# IMU_Breakout_Board.net
KiCad netlist of a schematic drawn in EAGLE
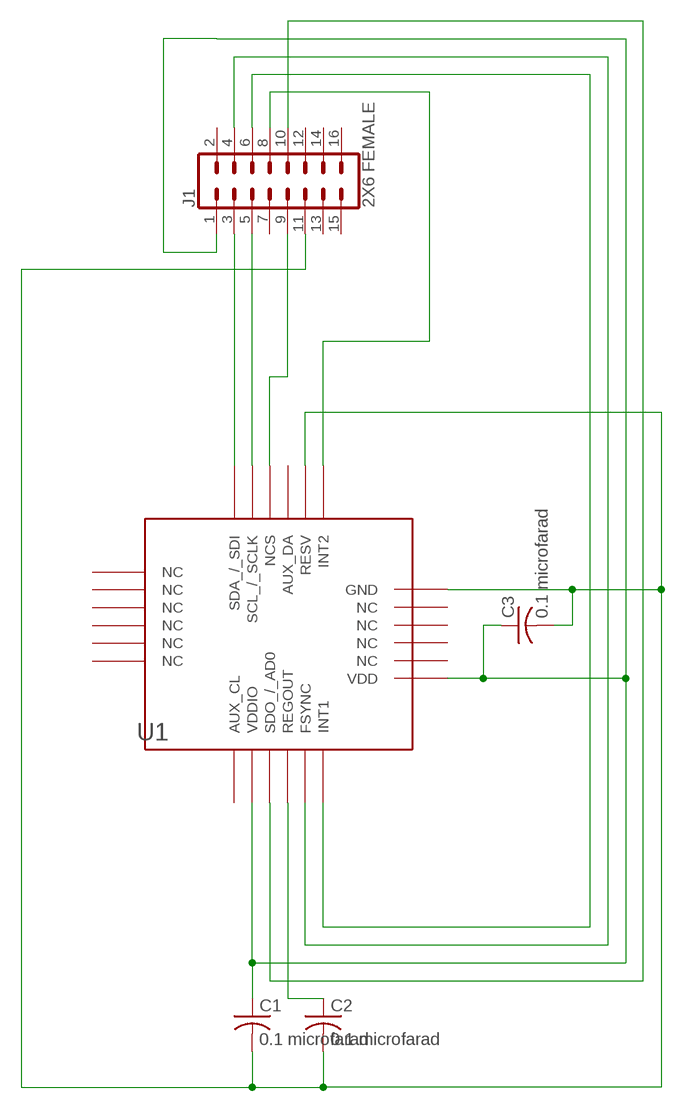
[diagram p0: schematic, sheet 1]

(export (version "E")
  (design (tool "Eeschema 10.0.6"))
  (components
    (comp (ref "C1")
      (value "0.1 microfarad")
      (footprint "eagle-import:C1206")
      (libsource (lib "eagle-import") (part "C-ALL_PACKAGESC1206"))
    )
    (comp (ref "C2")
      (value "0.1 microfarad")
      (footprint "eagle-import:C1206")
      (libsource (lib "eagle-import") (part "C-ALL_PACKAGESC1206"))
    )
    (comp (ref "C3")
      (value "0.1 microfarad")
      (footprint "eagle-import:C1206")
      (libsource (lib "eagle-import") (part "C-ALL_PACKAGESC1206"))
    )
    (comp (ref "J1")
      (value "2X6 FEMALE")
      (footprint "eagle-import:2X7")
      (libsource (lib "eagle-import") (part "SENSOR_BREAKOUTPTH_FEMALE"))
    )
    (comp (ref "U1")
      (value "ICM_20649")
      (footprint "eagle-import:ICM-20649")
      (libsource (lib "eagle-import") (part "ICM_20649"))
    )
  )
  (nets
    (net (code "1") (name "Net-(U1-FSYNC)") (class "Default")
      (node (ref "J1") (pin "4") (pinfunction "4_4") (pintype "passive"))
      (node (ref "U1") (pin "P4") (pinfunction "FSYNC_P4") (pintype "passive"))
    )
    (net (code "2") (name "Net-(U1-GND)") (class "Default")
      (node (ref "C1") (pin "2") (pinfunction "2_2") (pintype "passive"))
      (node (ref "C2") (pin "2") (pinfunction "2_2") (pintype "passive"))
      (node (ref "C3") (pin "2") (pinfunction "2_2") (pintype "passive"))
      (node (ref "J1") (pin "11") (pinfunction "11_11") (pintype "passive"))
      (node (ref "U1") (pin "P23") (pinfunction "GND_P23") (pintype "passive"))
      (node (ref "U1") (pin "P7") (pinfunction "RESV_P7") (pintype "passive"))
    )
    (net (code "3") (name "Net-(U1-INT1)") (class "Default")
      (node (ref "J1") (pin "6") (pinfunction "6_6") (pintype "passive"))
      (node (ref "U1") (pin "P5") (pinfunction "INT1_P5") (pintype "passive"))
    )
    (net (code "4") (name "Net-(U1-INT2)") (class "Default")
      (node (ref "J1") (pin "8") (pinfunction "8_8") (pintype "passive"))
      (node (ref "U1") (pin "P6") (pinfunction "INT2_P6") (pintype "passive"))
    )
    (net (code "5") (name "Net-(U1-NCS)") (class "Default")
      (node (ref "J1") (pin "9") (pinfunction "9_9") (pintype "passive"))
      (node (ref "U1") (pin "P9") (pinfunction "NCS_P9") (pintype "passive"))
    )
    (net (code "6") (name "Net-(U1-REGOUT)") (class "Default")
      (node (ref "C2") (pin "1") (pinfunction "1_1") (pintype "passive"))
      (node (ref "U1") (pin "P3") (pinfunction "REGOUT_P3") (pintype "passive"))
    )
    (net (code "7") (name "Net-(U1-SCL_{slash}_SCLK)") (class "Default")
      (node (ref "J1") (pin "5") (pinfunction "5_5") (pintype "passive"))
      (node (ref "U1") (pin "P10") (pinfunction "SCL_/_SCLK_P10") (pintype "passive"))
    )
    (net (code "8") (name "Net-(U1-SDA_{slash}_SDI)") (class "Default")
      (node (ref "J1") (pin "3") (pinfunction "3_3") (pintype "passive"))
      (node (ref "U1") (pin "P11") (pinfunction "SDA_/_SDI_P11") (pintype "passive"))
    )
    (net (code "9") (name "Net-(U1-SDO_{slash}_AD0)") (class "Default")
      (node (ref "J1") (pin "10") (pinfunction "10_10") (pintype "passive"))
      (node (ref "U1") (pin "P2") (pinfunction "SDO_/_AD0_P2") (pintype "passive"))
    )
    (net (code "10") (name "Net-(U1-VDD)") (class "Default")
      (node (ref "C1") (pin "1") (pinfunction "1_1") (pintype "passive"))
      (node (ref "C3") (pin "1") (pinfunction "1_1") (pintype "passive"))
      (node (ref "J1") (pin "1") (pinfunction "1_1") (pintype "passive"))
      (node (ref "U1") (pin "P1") (pinfunction "VDDIO_P1") (pintype "passive"))
      (node (ref "U1") (pin "P18") (pinfunction "VDD_P18") (pintype "passive"))
    )
    (net (code "11") (name "unconnected-(J1-Pad2)") (class "Default")
      (node (ref "J1") (pin "2") (pinfunction "2_2") (pintype "passive"))
    )
    (net (code "12") (name "unconnected-(J1-Pad7)") (class "Default")
      (node (ref "J1") (pin "7") (pinfunction "7_7") (pintype "passive"))
    )
    (net (code "13") (name "unconnected-(J1-Pad12)") (class "Default")
      (node (ref "J1") (pin "12") (pinfunction "12_12") (pintype "passive"))
    )
    (net (code "14") (name "unconnected-(J1-Pad13)") (class "Default")
      (node (ref "J1") (pin "13") (pinfunction "13_13") (pintype "passive"))
    )
    (net (code "15") (name "unconnected-(J1-Pad14)") (class "Default")
      (node (ref "J1") (pin "14") (pinfunction "14_14") (pintype "passive"))
    )
    (net (code "16") (name "unconnected-(J1-Pad15)") (class "Default")
      (node (ref "J1") (pin "15") (pinfunction "15_15") (pintype "passive"))
    )
    (net (code "17") (name "unconnected-(J1-Pad16)") (class "Default")
      (node (ref "J1") (pin "16") (pinfunction "16_16") (pintype "passive"))
    )
    (net (code "18") (name "unconnected-(U1-AUX_CL-PadP0)") (class "Default")
      (node (ref "U1") (pin "P0") (pinfunction "AUX_CL_P0") (pintype "passive"))
    )
    (net (code "19") (name "unconnected-(U1-AUX_DA-PadP8)") (class "Default")
      (node (ref "U1") (pin "P8") (pinfunction "AUX_DA_P8") (pintype "passive"))
    )
    (net (code "20") (name "unconnected-(U1-NC-PadP12)") (class "Default")
      (node (ref "U1") (pin "P12") (pinfunction "NC_P12") (pintype "passive"))
    )
    (net (code "21") (name "unconnected-(U1-NC-PadP13)") (class "Default")
      (node (ref "U1") (pin "P13") (pinfunction "NC_P13") (pintype "passive"))
    )
    (net (code "22") (name "unconnected-(U1-NC-PadP14)") (class "Default")
      (node (ref "U1") (pin "P14") (pinfunction "NC_P14") (pintype "passive"))
    )
    (net (code "23") (name "unconnected-(U1-NC-PadP15)") (class "Default")
      (node (ref "U1") (pin "P15") (pinfunction "NC_P15") (pintype "passive"))
    )
    (net (code "24") (name "unconnected-(U1-NC-PadP16)") (class "Default")
      (node (ref "U1") (pin "P16") (pinfunction "NC_P16") (pintype "passive"))
    )
    (net (code "25") (name "unconnected-(U1-NC-PadP17)") (class "Default")
      (node (ref "U1") (pin "P17") (pinfunction "NC_P17") (pintype "passive"))
    )
    (net (code "26") (name "unconnected-(U1-NC-PadP19)") (class "Default")
      (node (ref "U1") (pin "P19") (pinfunction "NC_P19") (pintype "passive"))
    )
    (net (code "27") (name "unconnected-(U1-NC-PadP20)") (class "Default")
      (node (ref "U1") (pin "P20") (pinfunction "NC_P20") (pintype "passive"))
    )
    (net (code "28") (name "unconnected-(U1-NC-PadP21)") (class "Default")
      (node (ref "U1") (pin "P21") (pinfunction "NC_P21") (pintype "passive"))
    )
    (net (code "29") (name "unconnected-(U1-NC-PadP22)") (class "Default")
      (node (ref "U1") (pin "P22") (pinfunction "NC_P22") (pintype "passive"))
    )
  )
)
